# termometr_1.net
KiCad netlist of a schematic drawn in EAGLE
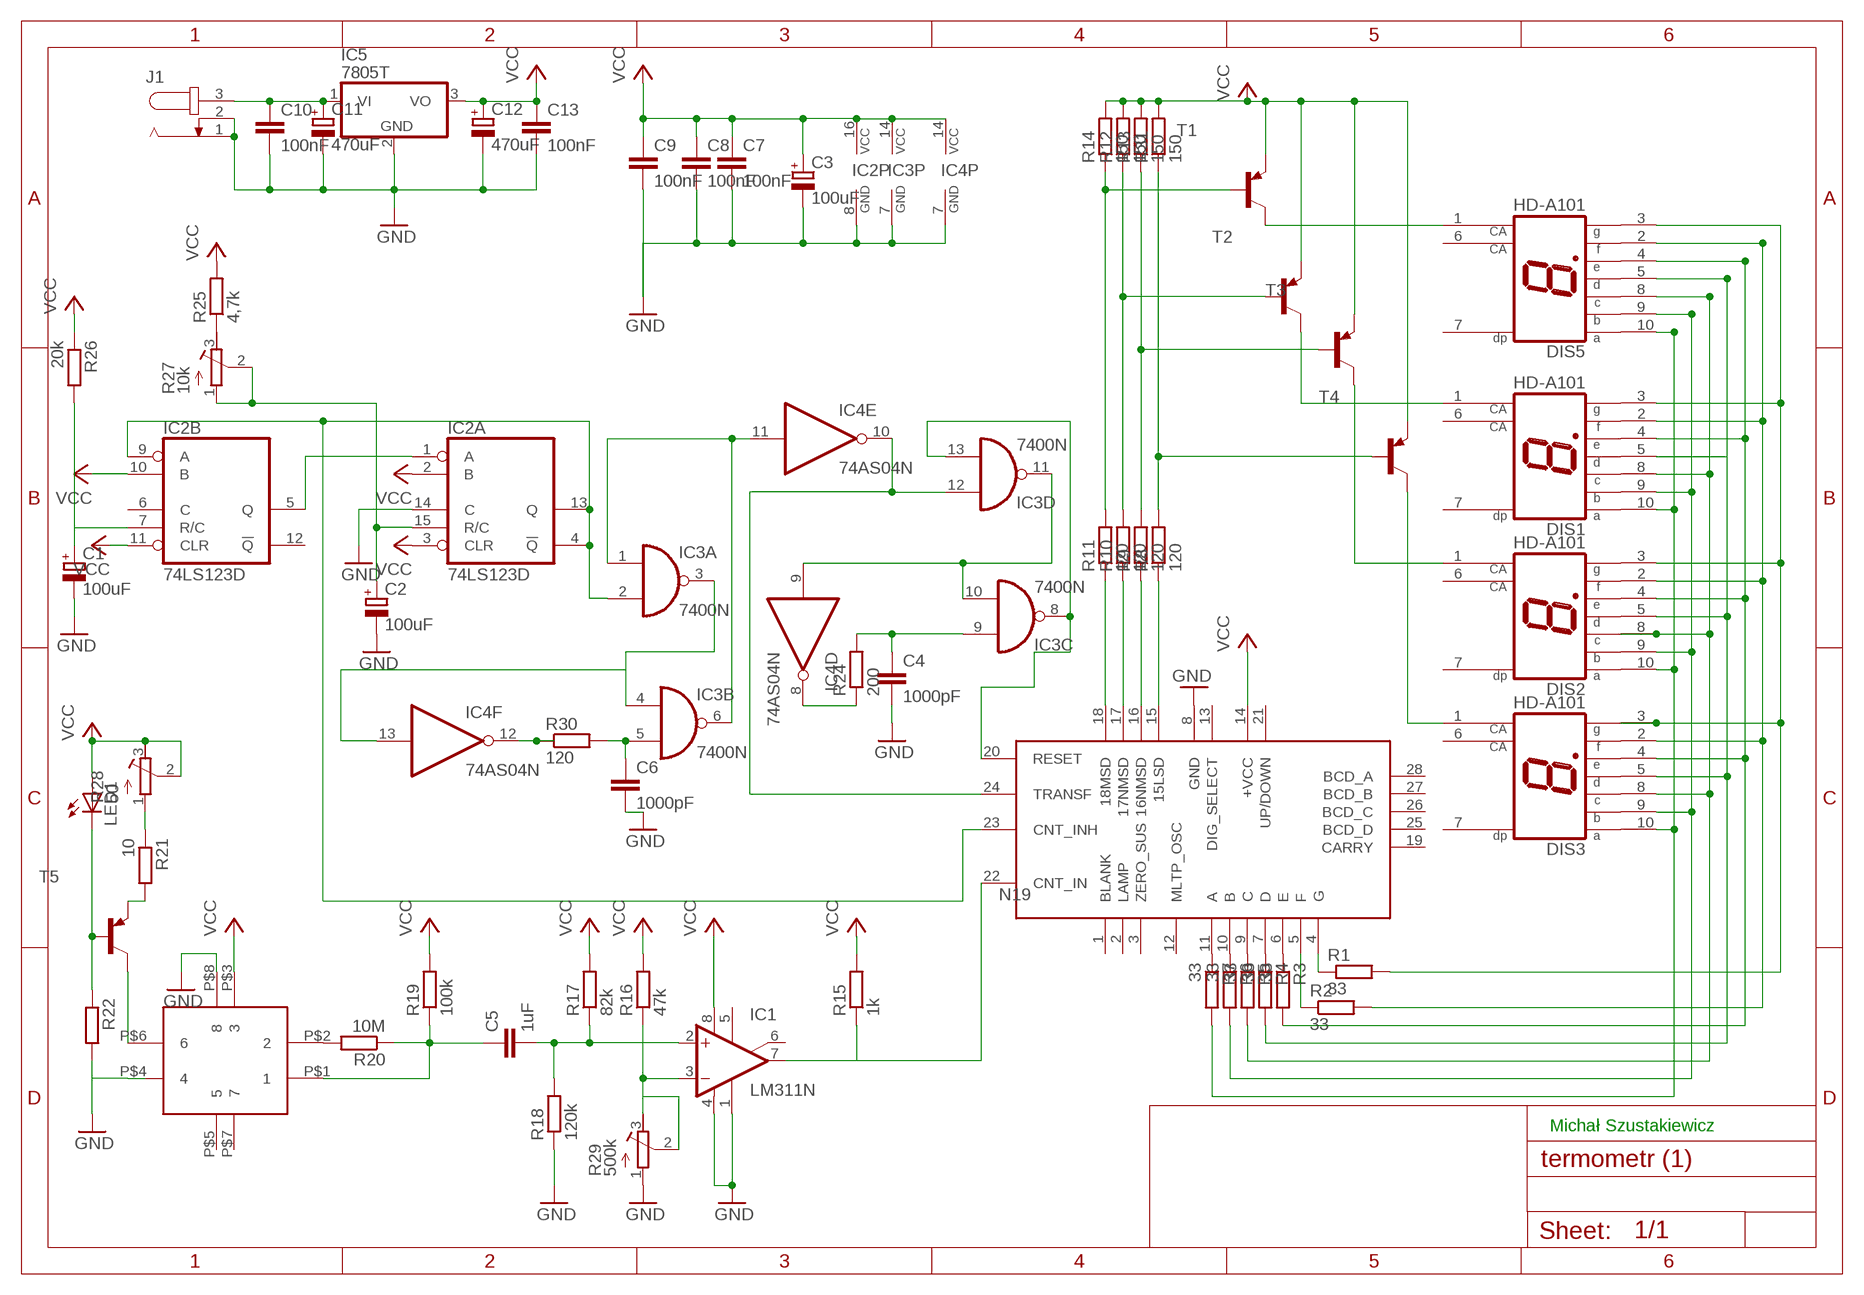
[diagram p0: schematic, sheet 1]

(export (version "E")
  (design (tool "Eeschema 10.0.6"))
  (components
    (comp (ref "C1")
      (value "100uF")
      (footprint "eagle-import:E2,5-5")
      (libsource (lib "eagle-import") (part "CPOL-EUE2.5-5"))
    )
    (comp (ref "C2")
      (value "100uF")
      (footprint "eagle-import:E2,5-5")
      (libsource (lib "eagle-import") (part "CPOL-EUE2.5-5"))
    )
    (comp (ref "C3")
      (value "100uF")
      (footprint "eagle-import:E2,5-5")
      (libsource (lib "eagle-import") (part "CPOL-EUE2.5-5"))
    )
    (comp (ref "C4")
      (value "1000pF")
      (footprint "eagle-import:C1206")
      (libsource (lib "eagle-import") (part "C-EUC1206"))
    )
    (comp (ref "C5")
      (value "1uF")
      (footprint "eagle-import:C1206")
      (libsource (lib "eagle-import") (part "C-EUC1206"))
    )
    (comp (ref "C6")
      (value "1000pF")
      (footprint "eagle-import:C1206")
      (libsource (lib "eagle-import") (part "C-EUC1206"))
    )
    (comp (ref "C7")
      (value "100nF")
      (footprint "eagle-import:C1206")
      (libsource (lib "eagle-import") (part "C-EUC1206"))
    )
    (comp (ref "C8")
      (value "100nF")
      (footprint "eagle-import:C1206")
      (libsource (lib "eagle-import") (part "C-EUC1206"))
    )
    (comp (ref "C9")
      (value "100nF")
      (footprint "eagle-import:C1206")
      (libsource (lib "eagle-import") (part "C-EUC1206"))
    )
    (comp (ref "C10")
      (value "100nF")
      (footprint "eagle-import:C1206")
      (libsource (lib "eagle-import") (part "C-EUC1206"))
    )
    (comp (ref "C11")
      (value "470uF")
      (footprint "eagle-import:E2,5-5")
      (libsource (lib "eagle-import") (part "CPOL-EUE2.5-5"))
    )
    (comp (ref "C12")
      (value "470uF")
      (footprint "eagle-import:E2,5-5")
      (libsource (lib "eagle-import") (part "CPOL-EUE2.5-5"))
    )
    (comp (ref "C13")
      (value "100nF")
      (footprint "eagle-import:C1206")
      (libsource (lib "eagle-import") (part "C-EUC1206"))
    )
    (comp (ref "DIS1")
      (value "HD-A101")
      (footprint "eagle-import:HDSP-A")
      (libsource (lib "eagle-import") (part "HD-A101"))
    )
    (comp (ref "DIS2")
      (value "HD-A101")
      (footprint "eagle-import:HDSP-A")
      (libsource (lib "eagle-import") (part "HD-A101"))
    )
    (comp (ref "DIS3")
      (value "HD-A101")
      (footprint "eagle-import:HDSP-A")
      (libsource (lib "eagle-import") (part "HD-A101"))
    )
    (comp (ref "DIS5")
      (value "HD-A101")
      (footprint "eagle-import:HDSP-A")
      (libsource (lib "eagle-import") (part "HD-A101"))
    )
    (comp (ref "IC1")
      (value "LM311N")
      (footprint "eagle-import:DIL08")
      (libsource (lib "eagle-import") (part "LM311N"))
    )
    (comp (ref "IC2")
      (value "74LS123D")
      (footprint "eagle-import:SO16")
      (libsource (lib "eagle-import") (part "74123DLS"))
    )
    (comp (ref "IC3")
      (value "7400N")
      (footprint "eagle-import:DIL14")
      (libsource (lib "eagle-import") (part "7400N"))
    )
    (comp (ref "IC4")
      (value "74AS04N")
      (footprint "eagle-import:DIL14")
      (libsource (lib "eagle-import") (part "7404NAS"))
    )
    (comp (ref "IC5")
      (value "7805T")
      (footprint "eagle-import:TO220H")
      (libsource (lib "eagle-import") (part "78T05"))
    )
    (comp (ref "J1")
      (value "JACK-PLUG0")
      (footprint "eagle-import:SPC4077")
      (libsource (lib "eagle-import") (part "JACK-PLUG0"))
    )
    (comp (ref "LED1")
      (value "LED5MM")
      (footprint "eagle-import:LED5MM")
      (libsource (lib "eagle-import") (part "LED5MM"))
    )
    (comp (ref "R1")
      (value "33")
      (footprint "eagle-import:M1206")
      (libsource (lib "eagle-import") (part "R-EU_M1206"))
    )
    (comp (ref "R2")
      (value "33")
      (footprint "eagle-import:M1206")
      (libsource (lib "eagle-import") (part "R-EU_M1206"))
    )
    (comp (ref "R3")
      (value "33")
      (footprint "eagle-import:M1206")
      (libsource (lib "eagle-import") (part "R-EU_M1206"))
    )
    (comp (ref "R4")
      (value "33")
      (footprint "eagle-import:M1206")
      (libsource (lib "eagle-import") (part "R-EU_M1206"))
    )
    (comp (ref "R5")
      (value "33")
      (footprint "eagle-import:M1206")
      (libsource (lib "eagle-import") (part "R-EU_M1206"))
    )
    (comp (ref "R6")
      (value "33")
      (footprint "eagle-import:M1206")
      (libsource (lib "eagle-import") (part "R-EU_M1206"))
    )
    (comp (ref "R7")
      (value "33")
      (footprint "eagle-import:M1206")
      (libsource (lib "eagle-import") (part "R-EU_M1206"))
    )
    (comp (ref "R8")
      (value "120")
      (footprint "eagle-import:M1206")
      (libsource (lib "eagle-import") (part "R-EU_M1206"))
    )
    (comp (ref "R9")
      (value "120")
      (footprint "eagle-import:M1206")
      (libsource (lib "eagle-import") (part "R-EU_M1206"))
    )
    (comp (ref "R10")
      (value "120")
      (footprint "eagle-import:M1206")
      (libsource (lib "eagle-import") (part "R-EU_M1206"))
    )
    (comp (ref "R11")
      (value "120")
      (footprint "eagle-import:M1206")
      (libsource (lib "eagle-import") (part "R-EU_M1206"))
    )
    (comp (ref "R12")
      (value "150")
      (footprint "eagle-import:M1206")
      (libsource (lib "eagle-import") (part "R-EU_M1206"))
    )
    (comp (ref "R13")
      (value "150")
      (footprint "eagle-import:M1206")
      (libsource (lib "eagle-import") (part "R-EU_M1206"))
    )
    (comp (ref "R14")
      (value "150")
      (footprint "eagle-import:M1206")
      (libsource (lib "eagle-import") (part "R-EU_M1206"))
    )
    (comp (ref "R15")
      (value "1k")
      (footprint "eagle-import:M1206")
      (libsource (lib "eagle-import") (part "R-EU_M1206"))
    )
    (comp (ref "R16")
      (value "47k")
      (footprint "eagle-import:M1206")
      (libsource (lib "eagle-import") (part "R-EU_M1206"))
    )
    (comp (ref "R17")
      (value "82k")
      (footprint "eagle-import:M1206")
      (libsource (lib "eagle-import") (part "R-EU_M1206"))
    )
    (comp (ref "R18")
      (value "120k")
      (footprint "eagle-import:M1206")
      (libsource (lib "eagle-import") (part "R-EU_M1206"))
    )
    (comp (ref "R19")
      (value "100k")
      (footprint "eagle-import:M1206")
      (libsource (lib "eagle-import") (part "R-EU_M1206"))
    )
    (comp (ref "R20")
      (value "10M")
      (footprint "eagle-import:M1206")
      (libsource (lib "eagle-import") (part "R-EU_M1206"))
    )
    (comp (ref "R21")
      (value "10")
      (footprint "eagle-import:M1206")
      (libsource (lib "eagle-import") (part "R-EU_M1206"))
    )
    (comp (ref "R22")
      (value "R-EU_M1206")
      (footprint "eagle-import:M1206")
      (libsource (lib "eagle-import") (part "R-EU_M1206"))
    )
    (comp (ref "R24")
      (value "200")
      (footprint "eagle-import:M1206")
      (libsource (lib "eagle-import") (part "R-EU_M1206"))
    )
    (comp (ref "R25")
      (value "4,7k")
      (footprint "eagle-import:M1206")
      (libsource (lib "eagle-import") (part "R-EU_M1206"))
    )
    (comp (ref "R26")
      (value "20k")
      (footprint "eagle-import:M1206")
      (libsource (lib "eagle-import") (part "R-EU_M1206"))
    )
    (comp (ref "R27")
      (value "10k")
      (footprint "eagle-import:RTRIM3202")
      (libsource (lib "eagle-import") (part "R-TRIMM3202"))
    )
    (comp (ref "R28")
      (value "50")
      (footprint "eagle-import:RTRIM3202")
      (libsource (lib "eagle-import") (part "R-TRIMM3202"))
    )
    (comp (ref "R29")
      (value "500k")
      (footprint "eagle-import:RTRIM3202")
      (libsource (lib "eagle-import") (part "R-TRIMM3202"))
    )
    (comp (ref "R30")
      (value "120")
      (footprint "eagle-import:M1206")
      (libsource (lib "eagle-import") (part "R-EU_M1206"))
    )
    (comp (ref "R31")
      (value "150")
      (footprint "eagle-import:M1206")
      (libsource (lib "eagle-import") (part "R-EU_M1206"))
    )
    (comp (ref "T1")
      (value "2N3906-PNP-TO92-EBC")
      (footprint "eagle-import:TO92-EBC")
      (libsource (lib "eagle-import") (part "-PNP-TO92-EBC2N3906"))
    )
    (comp (ref "T2")
      (value "2N3906-PNP-TO92-EBC")
      (footprint "eagle-import:TO92-EBC")
      (libsource (lib "eagle-import") (part "-PNP-TO92-EBC2N3906"))
    )
    (comp (ref "T3")
      (value "2N3906-PNP-TO92-EBC")
      (footprint "eagle-import:TO92-EBC")
      (libsource (lib "eagle-import") (part "-PNP-TO92-EBC2N3906"))
    )
    (comp (ref "T4")
      (value "2N3906-PNP-TO92-EBC")
      (footprint "eagle-import:TO92-EBC")
      (libsource (lib "eagle-import") (part "-PNP-TO92-EBC2N3906"))
    )
    (comp (ref "T5")
      (value "2N3906-PNP-TO92-EBC")
      (footprint "eagle-import:TO92-EBC")
      (libsource (lib "eagle-import") (part "-PNP-TO92-EBC2N3906"))
    )
    (comp (ref "U$1")
      (value "ZN1040E")
      (footprint "eagle-import:ZN1040E")
      (libsource (lib "eagle-import") (part "ZN1040E"))
    )
    (comp (ref "U$2")
      (value "HEDS_1200")
      (footprint "eagle-import:HEDS_1200")
      (libsource (lib "eagle-import") (part "HEDS_1200"))
    )
  )
  (nets
    (net (code "1") (name "/N19") (class "Default")
      (node (ref "IC2") (pin "13") (pinfunction "Q_13") (pintype "output"))
      (node (ref "IC2") (pin "4") (pinfunction "~{Q}_4") (pintype "output"))
      (node (ref "IC2") (pin "9") (pinfunction "A_9") (pintype "input"))
      (node (ref "IC3") (pin "2") (pinfunction "I1_2") (pintype "input"))
      (node (ref "U$1") (pin "23") (pinfunction "CNT_INH_23") (pintype "bidirectional"))
    )
    (net (code "2") (name "GND") (class "Default")
      (node (ref "C1") (pin "-") (pinfunction "-_-") (pintype "passive"))
      (node (ref "C10") (pin "2") (pinfunction "2_2") (pintype "passive"))
      (node (ref "C11") (pin "-") (pinfunction "-_-") (pintype "passive"))
      (node (ref "C12") (pin "-") (pinfunction "-_-") (pintype "passive"))
      (node (ref "C13") (pin "2") (pinfunction "2_2") (pintype "passive"))
      (node (ref "C2") (pin "-") (pinfunction "-_-") (pintype "passive"))
      (node (ref "C3") (pin "-") (pinfunction "-_-") (pintype "passive"))
      (node (ref "C4") (pin "2") (pinfunction "2_2") (pintype "passive"))
      (node (ref "C6") (pin "2") (pinfunction "2_2") (pintype "passive"))
      (node (ref "C7") (pin "2") (pinfunction "2_2") (pintype "passive"))
      (node (ref "C8") (pin "2") (pinfunction "2_2") (pintype "passive"))
      (node (ref "C9") (pin "2") (pinfunction "2_2") (pintype "passive"))
      (node (ref "IC1") (pin "1") (pinfunction "GND_1") (pintype "passive"))
      (node (ref "IC1") (pin "4") (pinfunction "V-_4") (pintype "power_in"))
      (node (ref "IC2") (pin "14") (pinfunction "C_14") (pintype "input"))
      (node (ref "IC2") (pin "8") (pinfunction "GND_8") (pintype "power_in"))
      (node (ref "IC3") (pin "7") (pinfunction "GND_7") (pintype "power_in"))
      (node (ref "IC4") (pin "7") (pinfunction "GND_7") (pintype "power_in"))
      (node (ref "IC5") (pin "2") (pinfunction "GND_2") (pintype "passive"))
      (node (ref "J1") (pin "1") (pinfunction "1_1") (pintype "passive"))
      (node (ref "J1") (pin "2") (pinfunction "2_2") (pintype "passive"))
      (node (ref "R18") (pin "1") (pinfunction "1_1") (pintype "passive"))
      (node (ref "R22") (pin "2") (pinfunction "2_2") (pintype "passive"))
      (node (ref "R29") (pin "1") (pinfunction "A_1") (pintype "passive"))
      (node (ref "U$1") (pin "8") (pinfunction "GND_8") (pintype "bidirectional"))
      (node (ref "U$2") (pin "P$4") (pinfunction "4_P$4") (pintype "bidirectional"))
      (node (ref "U$2") (pin "P$8") (pinfunction "8_P$8") (pintype "bidirectional"))
    )
    (net (code "3") (name "Net-(DIS1-A)") (class "Default")
      (node (ref "DIS1") (pin "10") (pinfunction "A_10") (pintype "passive"))
      (node (ref "DIS2") (pin "10") (pinfunction "A_10") (pintype "passive"))
      (node (ref "DIS3") (pin "10") (pinfunction "A_10") (pintype "passive"))
      (node (ref "DIS5") (pin "10") (pinfunction "A_10") (pintype "passive"))
      (node (ref "R7") (pin "2") (pinfunction "2_2") (pintype "passive"))
    )
    (net (code "4") (name "Net-(DIS1-B)") (class "Default")
      (node (ref "DIS1") (pin "9") (pinfunction "B_9") (pintype "passive"))
      (node (ref "DIS2") (pin "9") (pinfunction "B_9") (pintype "passive"))
      (node (ref "DIS3") (pin "9") (pinfunction "B_9") (pintype "passive"))
      (node (ref "DIS5") (pin "9") (pinfunction "B_9") (pintype "passive"))
      (node (ref "R6") (pin "2") (pinfunction "2_2") (pintype "passive"))
    )
    (net (code "5") (name "Net-(DIS1-C)") (class "Default")
      (node (ref "DIS1") (pin "8") (pinfunction "C_8") (pintype "passive"))
      (node (ref "DIS2") (pin "8") (pinfunction "C_8") (pintype "passive"))
      (node (ref "DIS3") (pin "8") (pinfunction "C_8") (pintype "passive"))
      (node (ref "DIS5") (pin "8") (pinfunction "C_8") (pintype "passive"))
      (node (ref "R5") (pin "2") (pinfunction "2_2") (pintype "passive"))
    )
    (net (code "6") (name "Net-(DIS1-CA-Pad1)") (class "Default")
      (node (ref "DIS1") (pin "1") (pinfunction "CA_1") (pintype "passive"))
      (node (ref "T2") (pin "C") (pinfunction "C_C") (pintype "passive"))
    )
    (net (code "7") (name "Net-(DIS1-D)") (class "Default")
      (node (ref "DIS1") (pin "5") (pinfunction "D_5") (pintype "passive"))
      (node (ref "DIS2") (pin "5") (pinfunction "D_5") (pintype "passive"))
      (node (ref "DIS3") (pin "5") (pinfunction "D_5") (pintype "passive"))
      (node (ref "DIS5") (pin "5") (pinfunction "D_5") (pintype "passive"))
      (node (ref "R4") (pin "2") (pinfunction "2_2") (pintype "passive"))
    )
    (net (code "8") (name "Net-(DIS1-E)") (class "Default")
      (node (ref "DIS1") (pin "4") (pinfunction "E_4") (pintype "passive"))
      (node (ref "DIS2") (pin "4") (pinfunction "E_4") (pintype "passive"))
      (node (ref "DIS3") (pin "4") (pinfunction "E_4") (pintype "passive"))
      (node (ref "DIS5") (pin "4") (pinfunction "E_4") (pintype "passive"))
      (node (ref "R3") (pin "2") (pinfunction "2_2") (pintype "passive"))
    )
    (net (code "9") (name "Net-(DIS1-F)") (class "Default")
      (node (ref "DIS1") (pin "2") (pinfunction "F_2") (pintype "passive"))
      (node (ref "DIS2") (pin "2") (pinfunction "F_2") (pintype "passive"))
      (node (ref "DIS3") (pin "2") (pinfunction "F_2") (pintype "passive"))
      (node (ref "DIS5") (pin "2") (pinfunction "F_2") (pintype "passive"))
      (node (ref "R2") (pin "2") (pinfunction "2_2") (pintype "passive"))
    )
    (net (code "10") (name "Net-(DIS1-G)") (class "Default")
      (node (ref "DIS1") (pin "3") (pinfunction "G_3") (pintype "passive"))
      (node (ref "DIS2") (pin "3") (pinfunction "G_3") (pintype "passive"))
      (node (ref "DIS3") (pin "3") (pinfunction "G_3") (pintype "passive"))
      (node (ref "DIS5") (pin "3") (pinfunction "G_3") (pintype "passive"))
      (node (ref "R1") (pin "2") (pinfunction "2_2") (pintype "passive"))
    )
    (net (code "11") (name "Net-(DIS2-CA-Pad1)") (class "Default")
      (node (ref "DIS2") (pin "1") (pinfunction "CA_1") (pintype "passive"))
      (node (ref "T3") (pin "C") (pinfunction "C_C") (pintype "passive"))
    )
    (net (code "12") (name "Net-(DIS3-CA-Pad1)") (class "Default")
      (node (ref "DIS3") (pin "1") (pinfunction "CA_1") (pintype "passive"))
      (node (ref "T4") (pin "C") (pinfunction "C_C") (pintype "passive"))
    )
    (net (code "13") (name "Net-(DIS5-CA-Pad1)") (class "Default")
      (node (ref "DIS5") (pin "1") (pinfunction "CA_1") (pintype "passive"))
      (node (ref "T1") (pin "C") (pinfunction "C_C") (pintype "passive"))
    )
    (net (code "14") (name "Net-(IC1-+IN)") (class "Default")
      (node (ref "C5") (pin "2") (pinfunction "2_2") (pintype "passive"))
      (node (ref "IC1") (pin "2") (pinfunction "+IN_2") (pintype "input"))
      (node (ref "R17") (pin "1") (pinfunction "1_1") (pintype "passive"))
      (node (ref "R18") (pin "2") (pinfunction "2_2") (pintype "passive"))
    )
    (net (code "15") (name "Net-(IC1--IN)") (class "Default")
      (node (ref "IC1") (pin "3") (pinfunction "-IN_3") (pintype "input"))
      (node (ref "R16") (pin "1") (pinfunction "1_1") (pintype "passive"))
      (node (ref "R29") (pin "2") (pinfunction "S_2") (pintype "passive"))
      (node (ref "R29") (pin "3") (pinfunction "E_3") (pintype "passive"))
    )
    (net (code "16") (name "Net-(IC1-OUT)") (class "Default")
      (node (ref "IC1") (pin "7") (pinfunction "OUT_7") (pintype "output"))
      (node (ref "R15") (pin "1") (pinfunction "1_1") (pintype "passive"))
      (node (ref "U$1") (pin "22") (pinfunction "CNT_IN_22") (pintype "bidirectional"))
    )
    (net (code "17") (name "Net-(IC2A-A)") (class "Default")
      (node (ref "IC2") (pin "1") (pinfunction "A_1") (pintype "input"))
      (node (ref "IC2") (pin "5") (pinfunction "Q_5") (pintype "output"))
    )
    (net (code "18") (name "Net-(IC2A-R{slash}C)") (class "Default")
      (node (ref "C2") (pin "+") (pinfunction "+_+") (pintype "passive"))
      (node (ref "IC2") (pin "15") (pinfunction "R/C_15") (pintype "input"))
      (node (ref "R27") (pin "1") (pinfunction "A_1") (pintype "passive"))
      (node (ref "R27") (pin "2") (pinfunction "S_2") (pintype "passive"))
    )
    (net (code "19") (name "Net-(IC2B-R{slash}C)") (class "Default")
      (node (ref "C1") (pin "+") (pinfunction "+_+") (pintype "passive"))
      (node (ref "IC2") (pin "7") (pinfunction "R/C_7") (pintype "input"))
      (node (ref "R26") (pin "2") (pinfunction "2_2") (pintype "passive"))
    )
    (net (code "20") (name "Net-(IC3A-I0)") (class "Default")
      (node (ref "IC3") (pin "1") (pinfunction "I0_1") (pintype "input"))
      (node (ref "IC3") (pin "6") (pinfunction "O_6") (pintype "output"))
      (node (ref "IC4") (pin "11") (pinfunction "I_11") (pintype "input"))
    )
    (net (code "21") (name "Net-(IC3A-O)") (class "Default")
      (node (ref "IC3") (pin "3") (pinfunction "O_3") (pintype "output"))
      (node (ref "IC3") (pin "4") (pinfunction "I0_4") (pintype "input"))
      (node (ref "IC4") (pin "13") (pinfunction "I_13") (pintype "input"))
    )
    (net (code "22") (name "Net-(IC3B-I1)") (class "Default")
      (node (ref "C6") (pin "1") (pinfunction "1_1") (pintype "passive"))
      (node (ref "IC3") (pin "5") (pinfunction "I1_5") (pintype "input"))
      (node (ref "R30") (pin "2") (pinfunction "2_2") (pintype "passive"))
    )
    (net (code "23") (name "Net-(IC3C-I0)") (class "Default")
      (node (ref "C4") (pin "1") (pinfunction "1_1") (pintype "passive"))
      (node (ref "IC3") (pin "9") (pinfunction "I0_9") (pintype "input"))
      (node (ref "R24") (pin "2") (pinfunction "2_2") (pintype "passive"))
    )
    (net (code "24") (name "Net-(IC3C-I1)") (class "Default")
      (node (ref "IC3") (pin "10") (pinfunction "I1_10") (pintype "input"))
      (node (ref "IC3") (pin "11") (pinfunction "O_11") (pintype "output"))
      (node (ref "IC4") (pin "9") (pinfunction "I_9") (pintype "input"))
    )
    (net (code "25") (name "Net-(IC3C-O)") (class "Default")
      (node (ref "IC3") (pin "13") (pinfunction "I1_13") (pintype "input"))
      (node (ref "IC3") (pin "8") (pinfunction "O_8") (pintype "output"))
      (node (ref "U$1") (pin "20") (pinfunction "RESET_20") (pintype "bidirectional"))
    )
    (net (code "26") (name "Net-(IC3D-I0)") (class "Default")
      (node (ref "IC3") (pin "12") (pinfunction "I0_12") (pintype "input"))
      (node (ref "IC4") (pin "10") (pinfunction "O_10") (pintype "output"))
      (node (ref "U$1") (pin "24") (pinfunction "TRANSF_24") (pintype "bidirectional"))
    )
    (net (code "27") (name "Net-(IC4D-O)") (class "Default")
      (node (ref "IC4") (pin "8") (pinfunction "O_8") (pintype "output"))
      (node (ref "R24") (pin "1") (pinfunction "1_1") (pintype "passive"))
    )
    (net (code "28") (name "Net-(IC4F-O)") (class "Default")
      (node (ref "IC4") (pin "12") (pinfunction "O_12") (pintype "output"))
      (node (ref "R30") (pin "1") (pinfunction "1_1") (pintype "passive"))
    )
    (net (code "29") (name "Net-(IC5-VI)") (class "Default")
      (node (ref "C10") (pin "1") (pinfunction "1_1") (pintype "passive"))
      (node (ref "C11") (pin "+") (pinfunction "+_+") (pintype "passive"))
      (node (ref "IC5") (pin "1") (pinfunction "VI_1") (pintype "input"))
      (node (ref "J1") (pin "3") (pinfunction "3_3") (pintype "passive"))
    )
    (net (code "30") (name "Net-(LED1-C)") (class "Default")
      (node (ref "LED1") (pin "K") (pinfunction "C_K") (pintype "passive"))
      (node (ref "R22") (pin "1") (pinfunction "1_1") (pintype "passive"))
      (node (ref "T5") (pin "B") (pinfunction "B_B") (pintype "passive"))
    )
    (net (code "31") (name "Net-(R10-Pad2)") (class "Default")
      (node (ref "R10") (pin "2") (pinfunction "2_2") (pintype "passive"))
      (node (ref "R12") (pin "1") (pinfunction "1_1") (pintype "passive"))
      (node (ref "T2") (pin "B") (pinfunction "B_B") (pintype "passive"))
    )
    (net (code "32") (name "Net-(R11-Pad2)") (class "Default")
      (node (ref "R11") (pin "2") (pinfunction "2_2") (pintype "passive"))
      (node (ref "R14") (pin "1") (pinfunction "1_1") (pintype "passive"))
      (node (ref "T1") (pin "B") (pinfunction "B_B") (pintype "passive"))
    )
    (net (code "33") (name "Net-(R13-Pad1)") (class "Default")
      (node (ref "R13") (pin "1") (pinfunction "1_1") (pintype "passive"))
      (node (ref "R9") (pin "2") (pinfunction "2_2") (pintype "passive"))
      (node (ref "T3") (pin "B") (pinfunction "B_B") (pintype "passive"))
    )
    (net (code "34") (name "Net-(R21-Pad2)") (class "Default")
      (node (ref "R21") (pin "2") (pinfunction "2_2") (pintype "passive"))
      (node (ref "T5") (pin "E") (pinfunction "E_E") (pintype "passive"))
    )
    (net (code "35") (name "Net-(R27-E)") (class "Default")
      (node (ref "R25") (pin "1") (pinfunction "1_1") (pintype "passive"))
      (node (ref "R27") (pin "3") (pinfunction "E_3") (pintype "passive"))
    )
    (net (code "36") (name "Net-(R28-A)") (class "Default")
      (node (ref "R21") (pin "1") (pinfunction "1_1") (pintype "passive"))
      (node (ref "R28") (pin "1") (pinfunction "A_1") (pintype "passive"))
    )
    (net (code "37") (name "Net-(R31-Pad1)") (class "Default")
      (node (ref "R31") (pin "1") (pinfunction "1_1") (pintype "passive"))
      (node (ref "R8") (pin "2") (pinfunction "2_2") (pintype "passive"))
      (node (ref "T4") (pin "B") (pinfunction "B_B") (pintype "passive"))
    )
    (net (code "38") (name "Net-(U$1-15LSD)") (class "Default")
      (node (ref "R8") (pin "1") (pinfunction "1_1") (pintype "passive"))
      (node (ref "U$1") (pin "15") (pinfunction "15LSD_15") (pintype "bidirectional"))
    )
    (net (code "39") (name "Net-(U$1-16NMSD)") (class "Default")
      (node (ref "R9") (pin "1") (pinfunction "1_1") (pintype "passive"))
      (node (ref "U$1") (pin "16") (pinfunction "16NMSD_16") (pintype "bidirectional"))
    )
    (net (code "40") (name "Net-(U$1-17NMSD)") (class "Default")
      (node (ref "R10") (pin "1") (pinfunction "1_1") (pintype "passive"))
      (node (ref "U$1") (pin "17") (pinfunction "17NMSD_17") (pintype "bidirectional"))
    )
    (net (code "41") (name "Net-(U$1-18MSD)") (class "Default")
      (node (ref "R11") (pin "1") (pinfunction "1_1") (pintype "passive"))
      (node (ref "U$1") (pin "18") (pinfunction "18MSD_18") (pintype "bidirectional"))
    )
    (net (code "42") (name "Net-(U$1-A)") (class "Default")
      (node (ref "R7") (pin "1") (pinfunction "1_1") (pintype "passive"))
      (node (ref "U$1") (pin "11") (pinfunction "A_11") (pintype "bidirectional"))
    )
    (net (code "43") (name "Net-(U$1-B)") (class "Default")
      (node (ref "R6") (pin "1") (pinfunction "1_1") (pintype "passive"))
      (node (ref "U$1") (pin "10") (pinfunction "B_10") (pintype "bidirectional"))
    )
    (net (code "44") (name "Net-(U$1-C)") (class "Default")
      (node (ref "R5") (pin "1") (pinfunction "1_1") (pintype "passive"))
      (node (ref "U$1") (pin "9") (pinfunction "C_9") (pintype "bidirectional"))
    )
    (net (code "45") (name "Net-(U$1-D)") (class "Default")
      (node (ref "R4") (pin "1") (pinfunction "1_1") (pintype "passive"))
      (node (ref "U$1") (pin "7") (pinfunction "D_7") (pintype "bidirectional"))
    )
    (net (code "46") (name "Net-(U$1-E)") (class "Default")
      (node (ref "R3") (pin "1") (pinfunction "1_1") (pintype "passive"))
      (node (ref "U$1") (pin "6") (pinfunction "E_6") (pintype "bidirectional"))
    )
    (net (code "47") (name "Net-(U$1-F)") (class "Default")
      (node (ref "R2") (pin "1") (pinfunction "1_1") (pintype "passive"))
      (node (ref "U$1") (pin "5") (pinfunction "F_5") (pintype "bidirectional"))
    )
    (net (code "48") (name "Net-(U$1-G)") (class "Default")
      (node (ref "R1") (pin "1") (pinfunction "1_1") (pintype "passive"))
      (node (ref "U$1") (pin "4") (pinfunction "G_4") (pintype "bidirectional"))
    )
    (net (code "49") (name "Net-(U$2-1)") (class "Default")
      (node (ref "C5") (pin "1") (pinfunction "1_1") (pintype "passive"))
      (node (ref "R19") (pin "1") (pinfunction "1_1") (pintype "passive"))
      (node (ref "R20") (pin "1") (pinfunction "1_1") (pintype "passive"))
      (node (ref "U$2") (pin "P$1") (pinfunction "1_P$1") (pintype "bidirectional"))
    )
    (net (code "50") (name "Net-(U$2-2)") (class "Default")
      (node (ref "R20") (pin "2") (pinfunction "2_2") (pintype "passive"))
      (node (ref "U$2") (pin "P$2") (pinfunction "2_P$2") (pintype "bidirectional"))
    )
    (net (code "51") (name "Net-(U$2-6)") (class "Default")
      (node (ref "T5") (pin "C") (pinfunction "C_C") (pintype "passive"))
      (node (ref "U$2") (pin "P$6") (pinfunction "6_P$6") (pintype "bidirectional"))
    )
    (net (code "52") (name "VCC") (class "Default")
      (node (ref "C12") (pin "+") (pinfunction "+_+") (pintype "passive"))
      (node (ref "C13") (pin "1") (pinfunction "1_1") (pintype "passive"))
      (node (ref "C3") (pin "+") (pinfunction "+_+") (pintype "passive"))
      (node (ref "C7") (pin "1") (pinfunction "1_1") (pintype "passive"))
      (node (ref "C8") (pin "1") (pinfunction "1_1") (pintype "passive"))
      (node (ref "C9") (pin "1") (pinfunction "1_1") (pintype "passive"))
      (node (ref "IC1") (pin "8") (pinfunction "V+_8") (pintype "power_in"))
      (node (ref "IC2") (pin "10") (pinfunction "B_10") (pintype "input"))
      (node (ref "IC2") (pin "11") (pinfunction "CLR_11") (pintype "input"))
      (node (ref "IC2") (pin "16") (pinfunction "VCC_16") (pintype "power_in"))
      (node (ref "IC2") (pin "2") (pinfunction "B_2") (pintype "input"))
      (node (ref "IC2") (pin "3") (pinfunction "CLR_3") (pintype "input"))
      (node (ref "IC3") (pin "14") (pinfunction "VCC_14") (pintype "power_in"))
      (node (ref "IC4") (pin "14") (pinfunction "VCC_14") (pintype "power_in"))
      (node (ref "IC5") (pin "3") (pinfunction "VO_3") (pintype "passive"))
      (node (ref "LED1") (pin "A") (pinfunction "A_A") (pintype "passive"))
      (node (ref "R12") (pin "2") (pinfunction "2_2") (pintype "passive"))
      (node (ref "R13") (pin "2") (pinfunction "2_2") (pintype "passive"))
      (node (ref "R14") (pin "2") (pinfunction "2_2") (pintype "passive"))
      (node (ref "R15") (pin "2") (pinfunction "2_2") (pintype "passive"))
      (node (ref "R16") (pin "2") (pinfunction "2_2") (pintype "passive"))
      (node (ref "R17") (pin "2") (pinfunction "2_2") (pintype "passive"))
      (node (ref "R19") (pin "2") (pinfunction "2_2") (pintype "passive"))
      (node (ref "R25") (pin "2") (pinfunction "2_2") (pintype "passive"))
      (node (ref "R26") (pin "1") (pinfunction "1_1") (pintype "passive"))
      (node (ref "R28") (pin "2") (pinfunction "S_2") (pintype "passive"))
      (node (ref "R28") (pin "3") (pinfunction "E_3") (pintype "passive"))
      (node (ref "R31") (pin "2") (pinfunction "2_2") (pintype "passive"))
      (node (ref "T1") (pin "E") (pinfunction "E_E") (pintype "passive"))
      (node (ref "T2") (pin "E") (pinfunction "E_E") (pintype "passive"))
      (node (ref "T3") (pin "E") (pinfunction "E_E") (pintype "passive"))
      (node (ref "T4") (pin "E") (pinfunction "E_E") (pintype "passive"))
      (node (ref "U$1") (pin "14") (pinfunction "+VCC_14") (pintype "bidirectional"))
      (node (ref "U$2") (pin "P$3") (pinfunction "3_P$3") (pintype "bidirectional"))
    )
    (net (code "53") (name "unconnected-(DIS1-CA-Pad6)") (class "Default")
      (node (ref "DIS1") (pin "6") (pinfunction "CA_6") (pintype "passive"))
    )
    (net (code "54") (name "unconnected-(DIS1-DP-Pad7)") (class "Default")
      (node (ref "DIS1") (pin "7") (pinfunction "DP_7") (pintype "passive"))
    )
    (net (code "55") (name "unconnected-(DIS2-CA-Pad6)") (class "Default")
      (node (ref "DIS2") (pin "6") (pinfunction "CA_6") (pintype "passive"))
    )
    (net (code "56") (name "unconnected-(DIS2-DP-Pad7)") (class "Default")
      (node (ref "DIS2") (pin "7") (pinfunction "DP_7") (pintype "passive"))
    )
    (net (code "57") (name "unconnected-(DIS3-CA-Pad6)") (class "Default")
      (node (ref "DIS3") (pin "6") (pinfunction "CA_6") (pintype "passive"))
    )
    (net (code "58") (name "unconnected-(DIS3-DP-Pad7)") (class "Default")
      (node (ref "DIS3") (pin "7") (pinfunction "DP_7") (pintype "passive"))
    )
    (net (code "59") (name "unconnected-(DIS5-CA-Pad6)") (class "Default")
      (node (ref "DIS5") (pin "6") (pinfunction "CA_6") (pintype "passive"))
    )
    (net (code "60") (name "unconnected-(DIS5-DP-Pad7)") (class "Default")
      (node (ref "DIS5") (pin "7") (pinfunction "DP_7") (pintype "passive"))
    )
    (net (code "61") (name "unconnected-(IC1-ON-Pad5)") (class "Default")
      (node (ref "IC1") (pin "5") (pinfunction "ON_5") (pintype "passive"))
    )
    (net (code "62") (name "unconnected-(IC1-ON{slash}STR-Pad6)") (class "Default")
      (node (ref "IC1") (pin "6") (pinfunction "ON/STR_6") (pintype "passive"))
    )
    (net (code "63") (name "unconnected-(IC2B-C-Pad6)") (class "Default")
      (node (ref "IC2") (pin "6") (pinfunction "C_6") (pintype "input"))
    )
    (net (code "64") (name "unconnected-(IC2B-~{Q}-Pad12)") (class "Default")
      (node (ref "IC2") (pin "12") (pinfunction "~{Q}_12") (pintype "output"))
    )
    (net (code "65") (name "unconnected-(U$1-BCD_A-Pad28)") (class "Default")
      (node (ref "U$1") (pin "28") (pinfunction "BCD_A_28") (pintype "bidirectional"))
    )
    (net (code "66") (name "unconnected-(U$1-BCD_B-Pad27)") (class "Default")
      (node (ref "U$1") (pin "27") (pinfunction "BCD_B_27") (pintype "bidirectional"))
    )
    (net (code "67") (name "unconnected-(U$1-BCD_C-Pad26)") (class "Default")
      (node (ref "U$1") (pin "26") (pinfunction "BCD_C_26") (pintype "bidirectional"))
    )
    (net (code "68") (name "unconnected-(U$1-BCD_D-Pad25)") (class "Default")
      (node (ref "U$1") (pin "25") (pinfunction "BCD_D_25") (pintype "bidirectional"))
    )
    (net (code "69") (name "unconnected-(U$1-BLANK-Pad1)") (class "Default")
      (node (ref "U$1") (pin "1") (pinfunction "BLANK_1") (pintype "bidirectional"))
    )
    (net (code "70") (name "unconnected-(U$1-CARRY-Pad19)") (class "Default")
      (node (ref "U$1") (pin "19") (pinfunction "CARRY_19") (pintype "bidirectional"))
    )
    (net (code "71") (name "unconnected-(U$1-DIG_SELECT-Pad13)") (class "Default")
      (node (ref "U$1") (pin "13") (pinfunction "DIG_SELECT_13") (pintype "bidirectional"))
    )
    (net (code "72") (name "unconnected-(U$1-LAMP-Pad2)") (class "Default")
      (node (ref "U$1") (pin "2") (pinfunction "LAMP_2") (pintype "bidirectional"))
    )
    (net (code "73") (name "unconnected-(U$1-MLTP_OSC-Pad12)") (class "Default")
      (node (ref "U$1") (pin "12") (pinfunction "MLTP_OSC_12") (pintype "bidirectional"))
    )
    (net (code "74") (name "unconnected-(U$1-UP{slash}DOWN-Pad21)") (class "Default")
      (node (ref "U$1") (pin "21") (pinfunction "UP/DOWN_21") (pintype "bidirectional"))
    )
    (net (code "75") (name "unconnected-(U$1-ZERO_SUS-Pad3)") (class "Default")
      (node (ref "U$1") (pin "3") (pinfunction "ZERO_SUS_3") (pintype "bidirectional"))
    )
    (net (code "76") (name "unconnected-(U$2-5-PadP$5)") (class "Default")
      (node (ref "U$2") (pin "P$5") (pinfunction "5_P$5") (pintype "bidirectional"))
    )
    (net (code "77") (name "unconnected-(U$2-7-PadP$7)") (class "Default")
      (node (ref "U$2") (pin "P$7") (pinfunction "7_P$7") (pintype "bidirectional"))
    )
  )
)
